# WORKSHOP.net
KiCad netlist of a schematic drawn in EAGLE
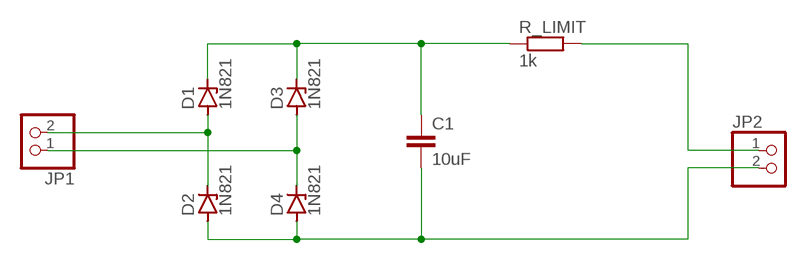
[diagram p0: schematic, sheet 1]

(export (version "E")
  (design (tool "Eeschema 10.0.6"))
  (components
    (comp (ref "C1")
      (value "10uF")
      (footprint "eagle-import:C2.5-6")
      (libsource (lib "eagle-import") (part "C2.5/6"))
    )
    (comp (ref "D1")
      (value "1N821")
      (footprint "eagle-import:DO35Z10")
      (libsource (lib "eagle-import") (part "1N821"))
    )
    (comp (ref "D2")
      (value "1N821")
      (footprint "eagle-import:DO35Z10")
      (libsource (lib "eagle-import") (part "1N821"))
    )
    (comp (ref "D3")
      (value "1N821")
      (footprint "eagle-import:DO35Z10")
      (libsource (lib "eagle-import") (part "1N821"))
    )
    (comp (ref "D4")
      (value "1N821")
      (footprint "eagle-import:DO35Z10")
      (libsource (lib "eagle-import") (part "1N821"))
    )
    (comp (ref "JP1")
      (value "PINHD-1X2")
      (footprint "eagle-import:1X02")
      (libsource (lib "eagle-import") (part "PINHD-1X2"))
    )
    (comp (ref "JP2")
      (value "PINHD-1X2")
      (footprint "eagle-import:1X02")
      (libsource (lib "eagle-import") (part "PINHD-1X2"))
    )
    (comp (ref "R_LIMIT")
      (value "1k")
      (footprint "eagle-import:0207_12")
      (libsource (lib "eagle-import") (part "R-EU_0207/12"))
    )
  )
  (nets
    (net (code "1") (name "Net-(C1-Pad1)") (class "Default")
      (node (ref "C1") (pin "1") (pinfunction "1_1") (pintype "passive"))
      (node (ref "D1") (pin "C") (pinfunction "C_C") (pintype "passive"))
      (node (ref "D3") (pin "C") (pinfunction "C_C") (pintype "passive"))
      (node (ref "R_LIMIT") (pin "1") (pinfunction "1_1") (pintype "passive"))
    )
    (net (code "2") (name "Net-(C1-Pad2)") (class "Default")
      (node (ref "C1") (pin "2") (pinfunction "2_2") (pintype "passive"))
      (node (ref "D2") (pin "A") (pinfunction "A_A") (pintype "passive"))
      (node (ref "D4") (pin "A") (pinfunction "A_A") (pintype "passive"))
      (node (ref "JP2") (pin "2") (pinfunction "2_2") (pintype "passive"))
    )
    (net (code "3") (name "Net-(D1-PadA)") (class "Default")
      (node (ref "D1") (pin "A") (pinfunction "A_A") (pintype "passive"))
      (node (ref "D2") (pin "C") (pinfunction "C_C") (pintype "passive"))
      (node (ref "JP1") (pin "2") (pinfunction "2_2") (pintype "passive"))
    )
    (net (code "4") (name "Net-(D3-PadA)") (class "Default")
      (node (ref "D3") (pin "A") (pinfunction "A_A") (pintype "passive"))
      (node (ref "D4") (pin "C") (pinfunction "C_C") (pintype "passive"))
      (node (ref "JP1") (pin "1") (pinfunction "1_1") (pintype "passive"))
    )
    (net (code "5") (name "Net-(JP2-Pad1)") (class "Default")
      (node (ref "JP2") (pin "1") (pinfunction "1_1") (pintype "passive"))
      (node (ref "R_LIMIT") (pin "2") (pinfunction "2_2") (pintype "passive"))
    )
  )
)
